# RS232_2xNPN_FTDI_PowerSel.net
KiCad netlist of a schematic drawn in EAGLE
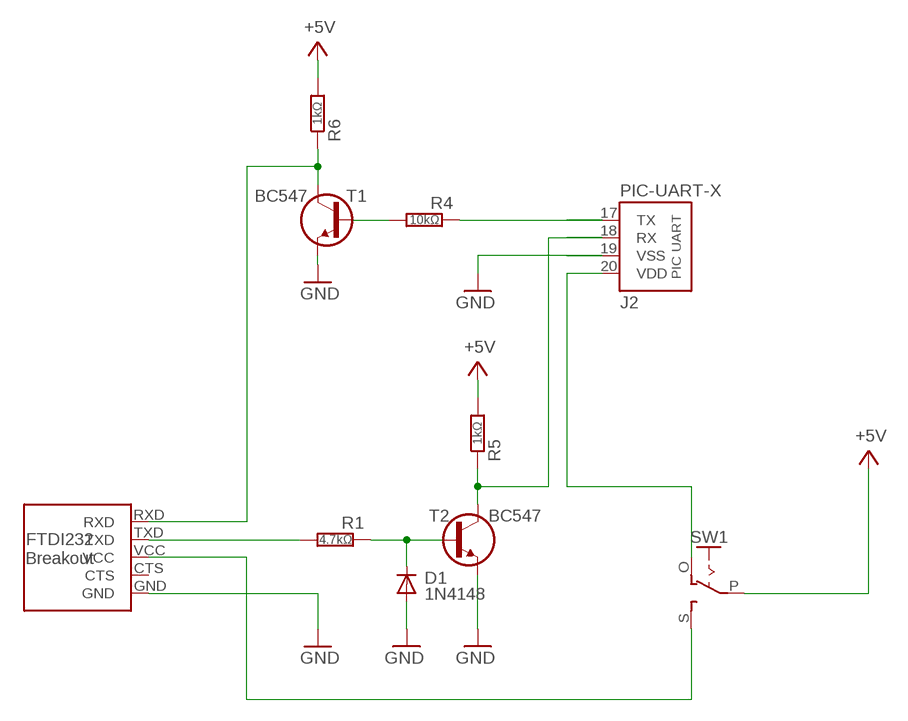
[diagram p0: schematic, sheet 1]

(export (version "E")
  (design (tool "Eeschema 10.0.6"))
  (components
    (comp (ref "D1")
      (value "1N4148")
      (footprint "eagle-import:DO34-5V")
      (libsource (lib "eagle-import") (part "1N414834-5V"))
    )
    (comp (ref "J1")
      (value "FTDI232-BO-5P-L")
      (footprint "eagle-import:FTDI232-BO-5-L")
      (libsource (lib "eagle-import") (part "FTDI232-BO-5P-L"))
    )
    (comp (ref "J2")
      (value "PIC-UART-X")
      (footprint "eagle-import:PIC-UART-X")
      (libsource (lib "eagle-import") (part "PIC-UART-X"))
    )
    (comp (ref "R1")
      (value "4.7kΩ")
      (footprint "eagle-import:0202_7")
      (libsource (lib "eagle-import") (part "R0202/7"))
    )
    (comp (ref "R4")
      (value "10kΩ")
      (footprint "eagle-import:0202_7")
      (libsource (lib "eagle-import") (part "R0202/7"))
    )
    (comp (ref "R5")
      (value "1kΩ")
      (footprint "eagle-import:0202_7-V")
      (libsource (lib "eagle-import") (part "R0202/7-V"))
    )
    (comp (ref "R6")
      (value "1kΩ")
      (footprint "eagle-import:0202_7")
      (libsource (lib "eagle-import") (part "R0202/7"))
    )
    (comp (ref "SW1")
      (value "SL-SW-1P-2T-JPSW")
      (footprint "eagle-import:JPSW-1P2T")
      (libsource (lib "eagle-import") (part "SL-SW-1P-2T-JPSW"))
    )
    (comp (ref "T1")
      (value "BC547")
      (footprint "eagle-import:TO92-CBE")
      (libsource (lib "eagle-import") (part "BC547CBE"))
    )
    (comp (ref "T2")
      (value "BC547")
      (footprint "eagle-import:TO92-CBE")
      (libsource (lib "eagle-import") (part "BC547CBE"))
    )
  )
  (nets
    (net (code "1") (name "+5V") (class "Default")
      (node (ref "R5") (pin "2") (pinfunction "2_2") (pintype "passive"))
      (node (ref "R6") (pin "2") (pinfunction "2_2") (pintype "passive"))
      (node (ref "SW1") (pin "P") (pinfunction "P_P") (pintype "passive"))
    )
    (net (code "2") (name "GND") (class "Default")
      (node (ref "D1") (pin "A") (pinfunction "A_A") (pintype "passive"))
      (node (ref "J1") (pin "GND") (pinfunction "GND_GND") (pintype "bidirectional"))
      (node (ref "J2") (pin "19") (pinfunction "VSS_19") (pintype "passive"))
      (node (ref "T1") (pin "E") (pinfunction "E_E") (pintype "passive"))
      (node (ref "T2") (pin "E") (pinfunction "E_E") (pintype "passive"))
    )
    (net (code "3") (name "Net-(D1-PadC)") (class "Default")
      (node (ref "D1") (pin "C") (pinfunction "C_C") (pintype "passive"))
      (node (ref "R1") (pin "1") (pinfunction "1_1") (pintype "passive"))
      (node (ref "T2") (pin "B") (pinfunction "B_B") (pintype "passive"))
    )
    (net (code "4") (name "Net-(J1-PadRXD)") (class "Default")
      (node (ref "J1") (pin "RXD") (pinfunction "RXD_RXD") (pintype "bidirectional"))
      (node (ref "R6") (pin "1") (pinfunction "1_1") (pintype "passive"))
      (node (ref "T1") (pin "C") (pinfunction "C_C") (pintype "passive"))
    )
    (net (code "5") (name "Net-(J1-PadTXD)") (class "Default")
      (node (ref "J1") (pin "TXD") (pinfunction "TXD_TXD") (pintype "bidirectional"))
      (node (ref "R1") (pin "2") (pinfunction "2_2") (pintype "passive"))
    )
    (net (code "6") (name "Net-(J1-PadVCC)") (class "Default")
      (node (ref "J1") (pin "VCC") (pinfunction "VCC_VCC") (pintype "bidirectional"))
      (node (ref "SW1") (pin "S") (pinfunction "S_S") (pintype "passive"))
    )
    (net (code "7") (name "Net-(J2-RX)") (class "Default")
      (node (ref "J2") (pin "18") (pinfunction "RX_18") (pintype "passive"))
      (node (ref "R5") (pin "1") (pinfunction "1_1") (pintype "passive"))
      (node (ref "T2") (pin "C") (pinfunction "C_C") (pintype "passive"))
    )
    (net (code "8") (name "Net-(J2-TX)") (class "Default")
      (node (ref "J2") (pin "17") (pinfunction "TX_17") (pintype "passive"))
      (node (ref "R4") (pin "1") (pinfunction "1_1") (pintype "passive"))
    )
    (net (code "9") (name "Net-(J2-VDD)") (class "Default")
      (node (ref "J2") (pin "20") (pinfunction "VDD_20") (pintype "passive"))
      (node (ref "SW1") (pin "O") (pinfunction "O_O") (pintype "passive"))
    )
    (net (code "10") (name "Net-(R4-Pad2)") (class "Default")
      (node (ref "R4") (pin "2") (pinfunction "2_2") (pintype "passive"))
      (node (ref "T1") (pin "B") (pinfunction "B_B") (pintype "passive"))
    )
    (net (code "11") (name "unconnected-(J1-PadCTS)") (class "Default")
      (node (ref "J1") (pin "CTS") (pinfunction "CTS_CTS") (pintype "bidirectional"))
    )
  )
)
